# voedingequ.net
KiCad netlist of a schematic drawn in EAGLE
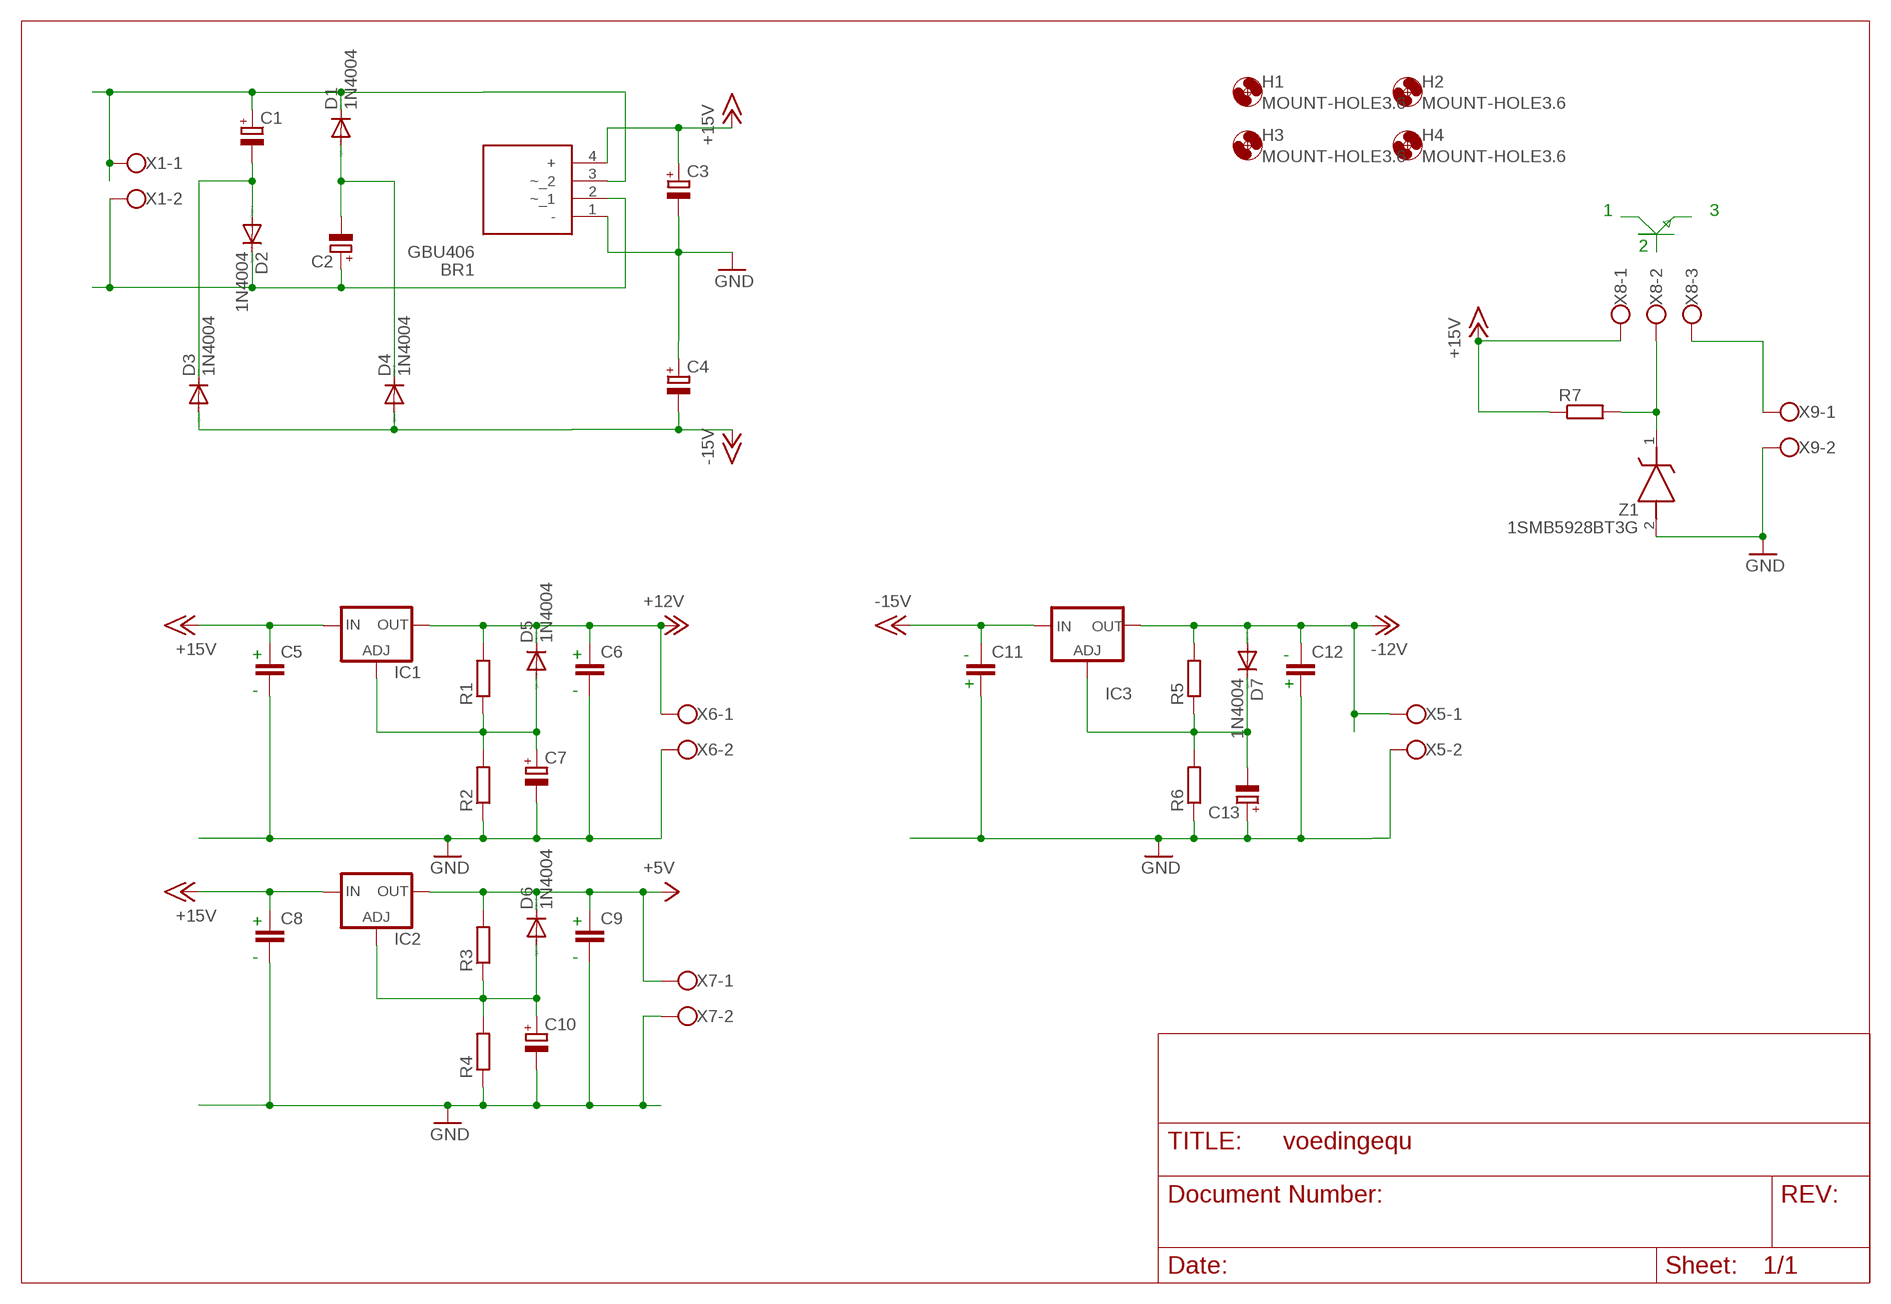
[diagram p0: schematic, sheet 1]

(export (version "E")
  (design (tool "Eeschema 10.0.6"))
  (components
    (comp (ref "BR1")
      (value "GBU406")
      (footprint "eagle-import:TO508P356X2205X2135-4P")
      (fields (field (name "MOUSER_PART_NUMBER") "621-GBU406"))
      (libsource (lib "eagle-import") (part "GBU406"))
    )
    (comp (ref "C1")
      (value "CPOL-EUE5-10.5")
      (footprint "eagle-import:E5-10,5")
      (libsource (lib "eagle-import") (part "CPOL-EUE5-10.5"))
    )
    (comp (ref "C2")
      (value "CPOL-EUE5-10.5")
      (footprint "eagle-import:E5-10,5")
      (libsource (lib "eagle-import") (part "CPOL-EUE5-10.5"))
    )
    (comp (ref "C3")
      (value "CPOL-EUE5-10.5")
      (footprint "eagle-import:E5-10,5")
      (libsource (lib "eagle-import") (part "CPOL-EUE5-10.5"))
    )
    (comp (ref "C4")
      (value "CPOL-EUE5-10.5")
      (footprint "eagle-import:E5-10,5")
      (libsource (lib "eagle-import") (part "CPOL-EUE5-10.5"))
    )
    (comp (ref "C5")
      (value "C-EUC0805")
      (footprint "eagle-import:C0805")
      (libsource (lib "eagle-import") (part "C-EUC0805"))
    )
    (comp (ref "C6")
      (value "C-EUC0805")
      (footprint "eagle-import:C0805")
      (libsource (lib "eagle-import") (part "C-EUC0805"))
    )
    (comp (ref "C7")
      (value "CPOL-EU153CLV-0505")
      (footprint "eagle-import:153CLV-0505")
      (libsource (lib "eagle-import") (part "CPOL-EU153CLV-0505"))
    )
    (comp (ref "C8")
      (value "C-EUC0805")
      (footprint "eagle-import:C0805")
      (libsource (lib "eagle-import") (part "C-EUC0805"))
    )
    (comp (ref "C9")
      (value "C-EUC0805")
      (footprint "eagle-import:C0805")
      (libsource (lib "eagle-import") (part "C-EUC0805"))
    )
    (comp (ref "C10")
      (value "CPOL-EU153CLV-0505")
      (footprint "eagle-import:153CLV-0505")
      (libsource (lib "eagle-import") (part "CPOL-EU153CLV-0505"))
    )
    (comp (ref "C11")
      (value "C-EUC0805")
      (footprint "eagle-import:C0805")
      (libsource (lib "eagle-import") (part "C-EUC0805"))
    )
    (comp (ref "C12")
      (value "C-EUC0805")
      (footprint "eagle-import:C0805")
      (libsource (lib "eagle-import") (part "C-EUC0805"))
    )
    (comp (ref "C13")
      (value "CPOL-EU153CLV-0505")
      (footprint "eagle-import:153CLV-0505")
      (libsource (lib "eagle-import") (part "CPOL-EU153CLV-0505"))
    )
    (comp (ref "D1")
      (value "1N4004")
      (footprint "eagle-import:DO41-10")
      (libsource (lib "eagle-import") (part "1N4004"))
    )
    (comp (ref "D2")
      (value "1N4004")
      (footprint "eagle-import:DO41-10")
      (libsource (lib "eagle-import") (part "1N4004"))
    )
    (comp (ref "D3")
      (value "1N4004")
      (footprint "eagle-import:DO41-10")
      (libsource (lib "eagle-import") (part "1N4004"))
    )
    (comp (ref "D4")
      (value "1N4004")
      (footprint "eagle-import:DO41-10")
      (libsource (lib "eagle-import") (part "1N4004"))
    )
    (comp (ref "D5")
      (value "1N4004")
      (footprint "eagle-import:DO41-10")
      (libsource (lib "eagle-import") (part "1N4004"))
    )
    (comp (ref "D6")
      (value "1N4004")
      (footprint "eagle-import:DO41-10")
      (libsource (lib "eagle-import") (part "1N4004"))
    )
    (comp (ref "D7")
      (value "1N4004")
      (footprint "eagle-import:DO41-10")
      (libsource (lib "eagle-import") (part "1N4004"))
    )
    (comp (ref "H1")
      (value "MOUNT-HOLE3.6")
      (footprint "eagle-import:3,6")
      (libsource (lib "eagle-import") (part "MOUNT-HOLE3.6"))
    )
    (comp (ref "H2")
      (value "MOUNT-HOLE3.6")
      (footprint "eagle-import:3,6")
      (libsource (lib "eagle-import") (part "MOUNT-HOLE3.6"))
    )
    (comp (ref "H3")
      (value "MOUNT-HOLE3.6")
      (footprint "eagle-import:3,6")
      (libsource (lib "eagle-import") (part "MOUNT-HOLE3.6"))
    )
    (comp (ref "H4")
      (value "MOUNT-HOLE3.6")
      (footprint "eagle-import:3,6")
      (libsource (lib "eagle-import") (part "MOUNT-HOLE3.6"))
    )
    (comp (ref "IC1")
      (value "LM317TS")
      (footprint "eagle-import:317TS")
      (libsource (lib "eagle-import") (part "LM317TS"))
    )
    (comp (ref "IC2")
      (value "LM317TS")
      (footprint "eagle-import:317TS")
      (libsource (lib "eagle-import") (part "LM317TS"))
    )
    (comp (ref "IC3")
      (value "LM337TS")
      (footprint "eagle-import:337TS")
      (libsource (lib "eagle-import") (part "LM337TS"))
    )
    (comp (ref "R1")
      (value "R-EU_R0805")
      (footprint "eagle-import:R0805")
      (libsource (lib "eagle-import") (part "R-EU_R0805"))
    )
    (comp (ref "R2")
      (value "R-EU_R0805")
      (footprint "eagle-import:R0805")
      (libsource (lib "eagle-import") (part "R-EU_R0805"))
    )
    (comp (ref "R3")
      (value "R-EU_R0805")
      (footprint "eagle-import:R0805")
      (libsource (lib "eagle-import") (part "R-EU_R0805"))
    )
    (comp (ref "R4")
      (value "R-EU_R0805")
      (footprint "eagle-import:R0805")
      (libsource (lib "eagle-import") (part "R-EU_R0805"))
    )
    (comp (ref "R5")
      (value "R-EU_R0805")
      (footprint "eagle-import:R0805")
      (libsource (lib "eagle-import") (part "R-EU_R0805"))
    )
    (comp (ref "R6")
      (value "R-EU_R0805")
      (footprint "eagle-import:R0805")
      (libsource (lib "eagle-import") (part "R-EU_R0805"))
    )
    (comp (ref "R7")
      (value "R-EU_R2512")
      (footprint "eagle-import:R2512")
      (libsource (lib "eagle-import") (part "R-EU_R2512"))
    )
    (comp (ref "X1")
      (value "W237-102")
      (footprint "eagle-import:W237-102")
      (libsource (lib "eagle-import") (part "W237-102"))
    )
    (comp (ref "X5")
      (value "W237-102")
      (footprint "eagle-import:W237-102")
      (libsource (lib "eagle-import") (part "W237-102"))
    )
    (comp (ref "X6")
      (value "W237-102")
      (footprint "eagle-import:W237-102")
      (libsource (lib "eagle-import") (part "W237-102"))
    )
    (comp (ref "X7")
      (value "W237-102")
      (footprint "eagle-import:W237-102")
      (libsource (lib "eagle-import") (part "W237-102"))
    )
    (comp (ref "X8")
      (value "W237-103")
      (footprint "eagle-import:W237-103")
      (libsource (lib "eagle-import") (part "W237-103"))
    )
    (comp (ref "X9")
      (value "W237-102")
      (footprint "eagle-import:W237-102")
      (libsource (lib "eagle-import") (part "W237-102"))
    )
    (comp (ref "Z1")
      (value "1SMB5928BT3G")
      (footprint "eagle-import:DIOM5436X247N")
      (fields
        (field (name "MOUSER_PART_NUMBER") "863-1SMB5928BT3G")
        (field (name "RS_PART_NUMBER") "7925414P")
      )
      (libsource (lib "eagle-import") (part "1SMB5928BT3G"))
    )
  )
  (nets
    (net (code "1") (name "+5V") (class "Default")
      (node (ref "C9") (pin "1") (pinfunction "1_1") (pintype "passive"))
      (node (ref "D6") (pin "C") (pinfunction "C_C") (pintype "passive"))
      (node (ref "IC2") (pin "2") (pinfunction "OUT_2") (pintype "passive"))
      (node (ref "R3") (pin "2") (pinfunction "2_2") (pintype "passive"))
      (node (ref "X7") (pin "1") (pinfunction "KL_1") (pintype "passive"))
    )
    (net (code "2") (name "+12V") (class "Default")
      (node (ref "C6") (pin "1") (pinfunction "1_1") (pintype "passive"))
      (node (ref "D5") (pin "C") (pinfunction "C_C") (pintype "passive"))
      (node (ref "IC1") (pin "2") (pinfunction "OUT_2") (pintype "passive"))
      (node (ref "R1") (pin "2") (pinfunction "2_2") (pintype "passive"))
      (node (ref "X6") (pin "1") (pinfunction "KL_1") (pintype "passive"))
    )
    (net (code "3") (name "+15V") (class "Default")
      (node (ref "BR1") (pin "4") (pinfunction "+_4") (pintype "bidirectional"))
      (node (ref "C3") (pin "+") (pinfunction "+_+") (pintype "passive"))
      (node (ref "C5") (pin "1") (pinfunction "1_1") (pintype "passive"))
      (node (ref "C8") (pin "1") (pinfunction "1_1") (pintype "passive"))
      (node (ref "IC1") (pin "3") (pinfunction "IN_3") (pintype "input"))
      (node (ref "IC2") (pin "3") (pinfunction "IN_3") (pintype "input"))
      (node (ref "R7") (pin "1") (pinfunction "1_1") (pintype "passive"))
      (node (ref "X8") (pin "1") (pinfunction "KL_1") (pintype "passive"))
    )
    (net (code "4") (name "-12V") (class "Default")
      (node (ref "C12") (pin "1") (pinfunction "1_1") (pintype "passive"))
      (node (ref "D7") (pin "A") (pinfunction "A_A") (pintype "passive"))
      (node (ref "IC3") (pin "3") (pinfunction "OUT_3") (pintype "passive"))
      (node (ref "R5") (pin "2") (pinfunction "2_2") (pintype "passive"))
      (node (ref "X5") (pin "1") (pinfunction "KL_1") (pintype "passive"))
    )
    (net (code "5") (name "-15V") (class "Default")
      (node (ref "C11") (pin "1") (pinfunction "1_1") (pintype "passive"))
      (node (ref "C4") (pin "-") (pinfunction "-_-") (pintype "passive"))
      (node (ref "D3") (pin "A") (pinfunction "A_A") (pintype "passive"))
      (node (ref "D4") (pin "A") (pinfunction "A_A") (pintype "passive"))
      (node (ref "IC3") (pin "2") (pinfunction "IN_2") (pintype "input"))
    )
    (net (code "6") (name "GND") (class "Default")
      (node (ref "BR1") (pin "1") (pinfunction "-_1") (pintype "bidirectional"))
      (node (ref "C10") (pin "-") (pinfunction "-_-") (pintype "passive"))
      (node (ref "C11") (pin "2") (pinfunction "2_2") (pintype "passive"))
      (node (ref "C12") (pin "2") (pinfunction "2_2") (pintype "passive"))
      (node (ref "C13") (pin "+") (pinfunction "+_+") (pintype "passive"))
      (node (ref "C3") (pin "-") (pinfunction "-_-") (pintype "passive"))
      (node (ref "C4") (pin "+") (pinfunction "+_+") (pintype "passive"))
      (node (ref "C5") (pin "2") (pinfunction "2_2") (pintype "passive"))
      (node (ref "C6") (pin "2") (pinfunction "2_2") (pintype "passive"))
      (node (ref "C7") (pin "-") (pinfunction "-_-") (pintype "passive"))
      (node (ref "C8") (pin "2") (pinfunction "2_2") (pintype "passive"))
      (node (ref "C9") (pin "2") (pinfunction "2_2") (pintype "passive"))
      (node (ref "R2") (pin "1") (pinfunction "1_1") (pintype "passive"))
      (node (ref "R4") (pin "1") (pinfunction "1_1") (pintype "passive"))
      (node (ref "R6") (pin "1") (pinfunction "1_1") (pintype "passive"))
      (node (ref "X5") (pin "2") (pinfunction "KL_2") (pintype "passive"))
      (node (ref "X6") (pin "2") (pinfunction "KL_2") (pintype "passive"))
      (node (ref "X7") (pin "2") (pinfunction "KL_2") (pintype "passive"))
      (node (ref "X9") (pin "2") (pinfunction "KL_2") (pintype "passive"))
      (node (ref "Z1") (pin "2") (pinfunction "A_2") (pintype "bidirectional"))
    )
    (net (code "7") (name "Net-(BR1-~{_1})") (class "Default")
      (node (ref "BR1") (pin "2") (pinfunction "~{_1}_2") (pintype "bidirectional"))
      (node (ref "C2") (pin "+") (pinfunction "+_+") (pintype "passive"))
      (node (ref "D2") (pin "C") (pinfunction "C_C") (pintype "passive"))
      (node (ref "X1") (pin "2") (pinfunction "KL_2") (pintype "passive"))
    )
    (net (code "8") (name "Net-(BR1-~{_2})") (class "Default")
      (node (ref "BR1") (pin "3") (pinfunction "~{_2}_3") (pintype "bidirectional"))
      (node (ref "C1") (pin "+") (pinfunction "+_+") (pintype "passive"))
      (node (ref "D1") (pin "C") (pinfunction "C_C") (pintype "passive"))
      (node (ref "X1") (pin "1") (pinfunction "KL_1") (pintype "passive"))
    )
    (net (code "9") (name "Net-(C1-Pad-)") (class "Default")
      (node (ref "C1") (pin "-") (pinfunction "-_-") (pintype "passive"))
      (node (ref "D2") (pin "A") (pinfunction "A_A") (pintype "passive"))
      (node (ref "D3") (pin "C") (pinfunction "C_C") (pintype "passive"))
    )
    (net (code "10") (name "Net-(C2-Pad-)") (class "Default")
      (node (ref "C2") (pin "-") (pinfunction "-_-") (pintype "passive"))
      (node (ref "D1") (pin "A") (pinfunction "A_A") (pintype "passive"))
      (node (ref "D4") (pin "C") (pinfunction "C_C") (pintype "passive"))
    )
    (net (code "11") (name "Net-(IC1-ADJ)") (class "Default")
      (node (ref "C7") (pin "+") (pinfunction "+_+") (pintype "passive"))
      (node (ref "D5") (pin "A") (pinfunction "A_A") (pintype "passive"))
      (node (ref "IC1") (pin "1") (pinfunction "ADJ_1") (pintype "input"))
      (node (ref "R1") (pin "1") (pinfunction "1_1") (pintype "passive"))
      (node (ref "R2") (pin "2") (pinfunction "2_2") (pintype "passive"))
    )
    (net (code "12") (name "Net-(IC2-ADJ)") (class "Default")
      (node (ref "C10") (pin "+") (pinfunction "+_+") (pintype "passive"))
      (node (ref "D6") (pin "A") (pinfunction "A_A") (pintype "passive"))
      (node (ref "IC2") (pin "1") (pinfunction "ADJ_1") (pintype "input"))
      (node (ref "R3") (pin "1") (pinfunction "1_1") (pintype "passive"))
      (node (ref "R4") (pin "2") (pinfunction "2_2") (pintype "passive"))
    )
    (net (code "13") (name "Net-(IC3-ADJ)") (class "Default")
      (node (ref "C13") (pin "-") (pinfunction "-_-") (pintype "passive"))
      (node (ref "D7") (pin "C") (pinfunction "C_C") (pintype "passive"))
      (node (ref "IC3") (pin "1") (pinfunction "ADJ_1") (pintype "input"))
      (node (ref "R5") (pin "1") (pinfunction "1_1") (pintype "passive"))
      (node (ref "R6") (pin "2") (pinfunction "2_2") (pintype "passive"))
    )
    (net (code "14") (name "Net-(X8B-KL)") (class "Default")
      (node (ref "R7") (pin "2") (pinfunction "2_2") (pintype "passive"))
      (node (ref "X8") (pin "2") (pinfunction "KL_2") (pintype "passive"))
      (node (ref "Z1") (pin "1") (pinfunction "K_1") (pintype "bidirectional"))
    )
    (net (code "15") (name "Net-(X8C-KL)") (class "Default")
      (node (ref "X8") (pin "3") (pinfunction "KL_3") (pintype "passive"))
      (node (ref "X9") (pin "1") (pinfunction "KL_1") (pintype "passive"))
    )
  )
)
